# Memory.net
KiCad netlist of a schematic drawn in Altium Designer
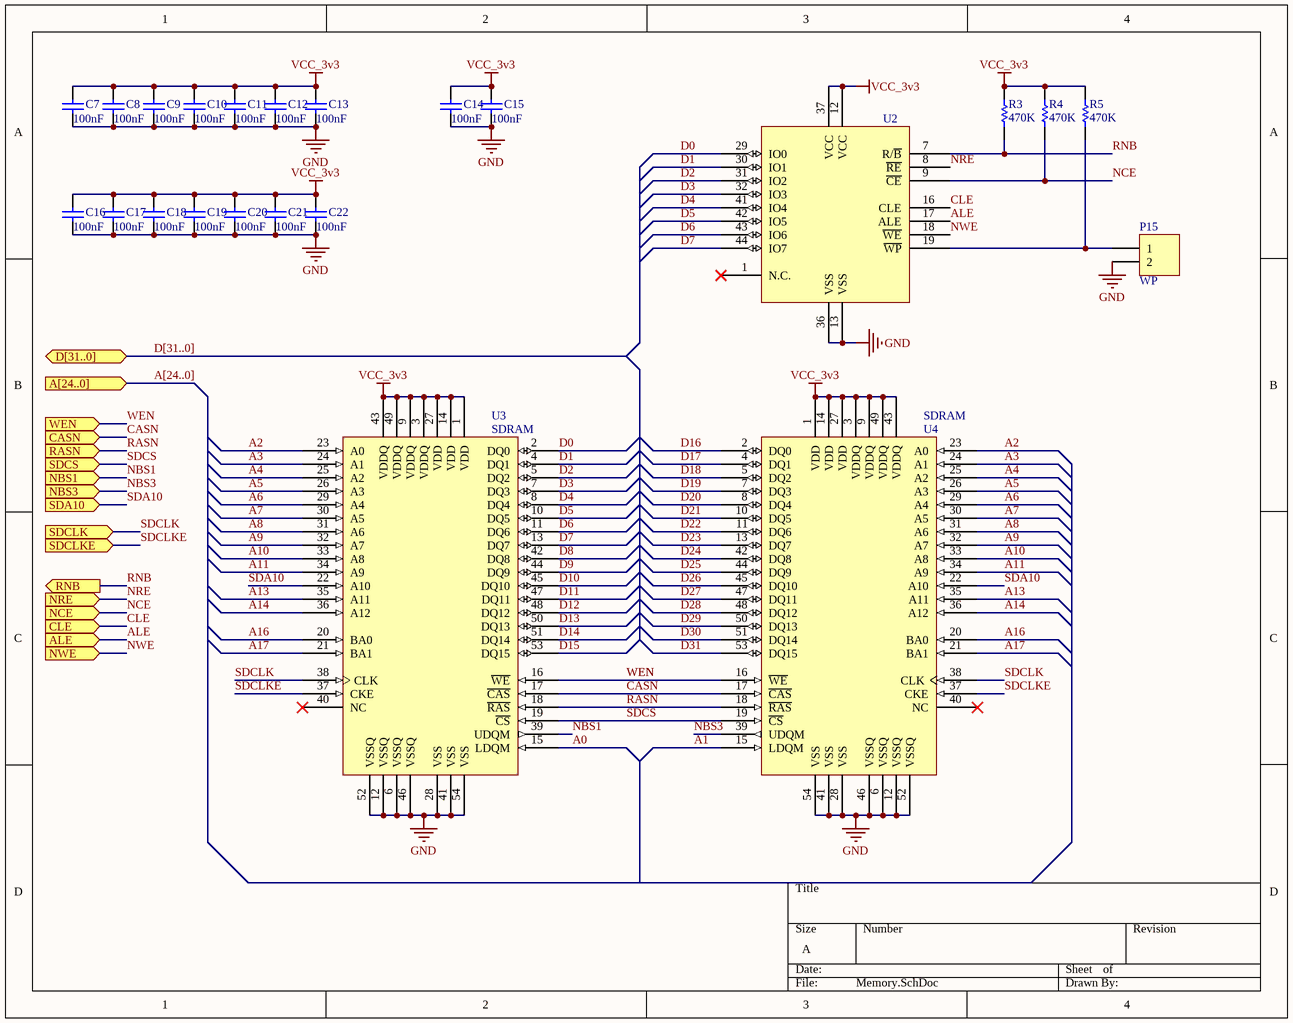
[diagram p0: Memory.SchDoc]

(export (version "E")
  (design (tool "Eeschema 10.0.6"))
  (components
    (comp (ref "C7")
      (value "100nF")
      (footprint "0603PKG")
      (description "Capacitor")
      (fields (field (name "Comment") "Cap") (field (name "PUBLISHER") "Altium Limited"))
      (libsource (lib "Miscellaneous Devices") (part "Cap"))
    )
    (comp (ref "C8")
      (value "100nF")
      (footprint "0603PKG")
      (description "Capacitor")
      (fields (field (name "Comment") "Cap") (field (name "PUBLISHER") "Altium Limited"))
      (libsource (lib "Miscellaneous Devices") (part "Cap"))
    )
    (comp (ref "C9")
      (value "100nF")
      (footprint "0603PKG")
      (description "Capacitor")
      (fields (field (name "Comment") "Cap") (field (name "PUBLISHER") "Altium Limited"))
      (libsource (lib "Miscellaneous Devices") (part "Cap"))
    )
    (comp (ref "C10")
      (value "100nF")
      (footprint "0603PKG")
      (description "Capacitor")
      (fields (field (name "Comment") "Cap") (field (name "PUBLISHER") "Altium Limited"))
      (libsource (lib "Miscellaneous Devices") (part "Cap"))
    )
    (comp (ref "C11")
      (value "100nF")
      (footprint "0603PKG")
      (description "Capacitor")
      (fields (field (name "Comment") "Cap") (field (name "PUBLISHER") "Altium Limited"))
      (libsource (lib "Miscellaneous Devices") (part "Cap"))
    )
    (comp (ref "C12")
      (value "100nF")
      (footprint "0603PKG")
      (description "Capacitor")
      (fields (field (name "Comment") "Cap") (field (name "PUBLISHER") "Altium Limited"))
      (libsource (lib "Miscellaneous Devices") (part "Cap"))
    )
    (comp (ref "C13")
      (value "100nF")
      (footprint "0603PKG")
      (description "Capacitor")
      (fields (field (name "Comment") "Cap") (field (name "PUBLISHER") "Altium Limited"))
      (libsource (lib "Miscellaneous Devices") (part "Cap"))
    )
    (comp (ref "C14")
      (value "100nF")
      (footprint "C0805")
      (description "Capacitor")
      (fields (field (name "Comment") "Cap") (field (name "PUBLISHER") "Altium Limited"))
      (libsource (lib "Miscellaneous Devices") (part "Cap"))
    )
    (comp (ref "C15")
      (value "100nF")
      (footprint "C0805")
      (description "Capacitor")
      (fields (field (name "Comment") "Cap") (field (name "PUBLISHER") "Altium Limited"))
      (libsource (lib "Miscellaneous Devices") (part "Cap"))
    )
    (comp (ref "C16")
      (value "100nF")
      (footprint "0603PKG")
      (description "Capacitor")
      (fields (field (name "Comment") "Cap") (field (name "PUBLISHER") "Altium Limited"))
      (libsource (lib "Miscellaneous Devices") (part "Cap"))
    )
    (comp (ref "C17")
      (value "100nF")
      (footprint "0603PKG")
      (description "Capacitor")
      (fields (field (name "Comment") "Cap") (field (name "PUBLISHER") "Altium Limited"))
      (libsource (lib "Miscellaneous Devices") (part "Cap"))
    )
    (comp (ref "C18")
      (value "100nF")
      (footprint "0603PKG")
      (description "Capacitor")
      (fields (field (name "Comment") "Cap") (field (name "PUBLISHER") "Altium Limited"))
      (libsource (lib "Miscellaneous Devices") (part "Cap"))
    )
    (comp (ref "C19")
      (value "100nF")
      (footprint "0603PKG")
      (description "Capacitor")
      (fields (field (name "Comment") "Cap") (field (name "PUBLISHER") "Altium Limited"))
      (libsource (lib "Miscellaneous Devices") (part "Cap"))
    )
    (comp (ref "C20")
      (value "100nF")
      (footprint "0603PKG")
      (description "Capacitor")
      (fields (field (name "Comment") "Cap") (field (name "PUBLISHER") "Altium Limited"))
      (libsource (lib "Miscellaneous Devices") (part "Cap"))
    )
    (comp (ref "C21")
      (value "100nF")
      (footprint "0603PKG")
      (description "Capacitor")
      (fields (field (name "Comment") "Cap") (field (name "PUBLISHER") "Altium Limited"))
      (libsource (lib "Miscellaneous Devices") (part "Cap"))
    )
    (comp (ref "C22")
      (value "100nF")
      (footprint "0603PKG")
      (description "Capacitor")
      (fields (field (name "Comment") "Cap") (field (name "PUBLISHER") "Altium Limited"))
      (libsource (lib "Miscellaneous Devices") (part "Cap"))
    )
    (comp (ref "P15")
      (value "WP")
      (footprint "HDR1X2")
      (description "Header, 2-Pin")
      (fields (field (name "PUBLISHER") "Altium Limited"))
      (libsource (lib "Miscellaneous Connectors") (part "Header 2"))
    )
    (comp (ref "R3")
      (value "470K")
      (footprint "C0805")
      (description "Semiconductor Resistor")
      (fields (field (name "Comment") "Res Semi") (field (name "PUBLISHER") "Altium Limited"))
      (libsource (lib "Miscellaneous Devices") (part "Res Semi"))
    )
    (comp (ref "R4")
      (value "470K")
      (footprint "C0805")
      (description "Semiconductor Resistor")
      (fields (field (name "Comment") "Res Semi") (field (name "PUBLISHER") "Altium Limited"))
      (libsource (lib "Miscellaneous Devices") (part "Res Semi"))
    )
    (comp (ref "R5")
      (value "470K")
      (footprint "C0805")
      (description "Semiconductor Resistor")
      (fields (field (name "Comment") "Res Semi") (field (name "PUBLISHER") "Altium Limited"))
      (libsource (lib "Miscellaneous Devices") (part "Res Semi"))
    )
    (comp (ref "U2")
      (value "NAND FLASH")
      (footprint "TSSOP-48")
      (libsource (lib "Connector_IntLib") (part "K9F2G08U0A"))
    )
    (comp (ref "U3") (value "SDRAM") (footprint "TSOP54_Pin") (libsource (lib "") (part "K4S561632C_1")))
    (comp (ref "U4")
      (value "SDRAM")
      (footprint "TSOP54_Pin")
      (libsource (lib "Conn_Schlib") (part "K4S561632C"))
    )
  )
  (nets
    (net (code "10") (name "/A0") (class "Default")
      (node (ref "U3") (pin "15") (pinfunction "LDQM_15") (pintype "input"))
    )
    (net (code "11") (name "/A1") (class "Default")
      (node (ref "U4") (pin "15") (pinfunction "LDQM_15") (pintype "input"))
    )
    (net (code "12") (name "/A2") (class "Default")
      (node (ref "U3") (pin "23") (pinfunction "A0_23") (pintype "input"))
      (node (ref "U4") (pin "23") (pinfunction "A0_23") (pintype "input"))
    )
    (net (code "13") (name "/A3") (class "Default")
      (node (ref "U3") (pin "24") (pinfunction "A1_24") (pintype "input"))
      (node (ref "U4") (pin "24") (pinfunction "A1_24") (pintype "input"))
    )
    (net (code "14") (name "/A4") (class "Default")
      (node (ref "U3") (pin "25") (pinfunction "A2_25") (pintype "input"))
      (node (ref "U4") (pin "25") (pinfunction "A2_25") (pintype "input"))
    )
    (net (code "15") (name "/A5") (class "Default")
      (node (ref "U3") (pin "26") (pinfunction "A3_26") (pintype "input"))
      (node (ref "U4") (pin "26") (pinfunction "A3_26") (pintype "input"))
    )
    (net (code "16") (name "/A6") (class "Default")
      (node (ref "U3") (pin "29") (pinfunction "A4_29") (pintype "input"))
      (node (ref "U4") (pin "29") (pinfunction "A4_29") (pintype "input"))
    )
    (net (code "17") (name "/A7") (class "Default")
      (node (ref "U3") (pin "30") (pinfunction "A5_30") (pintype "input"))
      (node (ref "U4") (pin "30") (pinfunction "A5_30") (pintype "input"))
    )
    (net (code "18") (name "/A8") (class "Default")
      (node (ref "U3") (pin "31") (pinfunction "A6_31") (pintype "input"))
      (node (ref "U4") (pin "31") (pinfunction "A6_31") (pintype "input"))
    )
    (net (code "19") (name "/A9") (class "Default")
      (node (ref "U3") (pin "32") (pinfunction "A7_32") (pintype "input"))
      (node (ref "U4") (pin "32") (pinfunction "A7_32") (pintype "input"))
    )
    (net (code "20") (name "/A10") (class "Default")
      (node (ref "U3") (pin "33") (pinfunction "A8_33") (pintype "input"))
      (node (ref "U4") (pin "33") (pinfunction "A8_33") (pintype "input"))
    )
    (net (code "21") (name "/A11") (class "Default")
      (node (ref "U3") (pin "34") (pinfunction "A9_34") (pintype "input"))
      (node (ref "U4") (pin "34") (pinfunction "A9_34") (pintype "input"))
    )
    (net (code "22") (name "/A13") (class "Default")
      (node (ref "U3") (pin "35") (pinfunction "A11_35") (pintype "input"))
      (node (ref "U4") (pin "35") (pinfunction "A11_35") (pintype "input"))
    )
    (net (code "23") (name "/A14") (class "Default")
      (node (ref "U3") (pin "36") (pinfunction "A12_36") (pintype "input"))
      (node (ref "U4") (pin "36") (pinfunction "A12_36") (pintype "input"))
    )
    (net (code "24") (name "/A16") (class "Default")
      (node (ref "U3") (pin "20") (pinfunction "BA0_20") (pintype "input"))
      (node (ref "U4") (pin "20") (pinfunction "BA0_20") (pintype "input"))
    )
    (net (code "25") (name "/A17") (class "Default")
      (node (ref "U3") (pin "21") (pinfunction "BA1_21") (pintype "input"))
      (node (ref "U4") (pin "21") (pinfunction "BA1_21") (pintype "input"))
    )
    (net (code "26") (name "/ALE") (class "Default")
      (node (ref "U2") (pin "17") (pinfunction "ALE_17") (pintype "passive"))
    )
    (net (code "28") (name "/CASN") (class "Default")
      (node (ref "U3") (pin "17") (pinfunction "~{CAS}_17") (pintype "input"))
      (node (ref "U4") (pin "17") (pinfunction "~{CAS}_17") (pintype "input"))
    )
    (net (code "29") (name "/CLE") (class "Default")
      (node (ref "U2") (pin "16") (pinfunction "CLE_16") (pintype "passive"))
    )
    (net (code "30") (name "/D0") (class "Default")
      (node (ref "U2") (pin "29") (pinfunction "IO0_29") (pintype "bidirectional"))
      (node (ref "U3") (pin "2") (pinfunction "DQ0_2") (pintype "bidirectional"))
    )
    (net (code "31") (name "/D1") (class "Default")
      (node (ref "U2") (pin "30") (pinfunction "IO1_30") (pintype "bidirectional"))
      (node (ref "U3") (pin "4") (pinfunction "DQ1_4") (pintype "bidirectional"))
    )
    (net (code "32") (name "/D2") (class "Default")
      (node (ref "U2") (pin "31") (pinfunction "IO2_31") (pintype "bidirectional"))
      (node (ref "U3") (pin "5") (pinfunction "DQ2_5") (pintype "bidirectional"))
    )
    (net (code "33") (name "/D3") (class "Default")
      (node (ref "U2") (pin "32") (pinfunction "IO3_32") (pintype "bidirectional"))
      (node (ref "U3") (pin "7") (pinfunction "DQ3_7") (pintype "bidirectional"))
    )
    (net (code "34") (name "/D4") (class "Default")
      (node (ref "U2") (pin "41") (pinfunction "IO4_41") (pintype "bidirectional"))
      (node (ref "U3") (pin "8") (pinfunction "DQ4_8") (pintype "bidirectional"))
    )
    (net (code "35") (name "/D5") (class "Default")
      (node (ref "U2") (pin "42") (pinfunction "IO5_42") (pintype "bidirectional"))
      (node (ref "U3") (pin "10") (pinfunction "DQ5_10") (pintype "bidirectional"))
    )
    (net (code "36") (name "/D6") (class "Default")
      (node (ref "U2") (pin "43") (pinfunction "IO6_43") (pintype "bidirectional"))
      (node (ref "U3") (pin "11") (pinfunction "DQ6_11") (pintype "bidirectional"))
    )
    (net (code "37") (name "/D7") (class "Default")
      (node (ref "U2") (pin "44") (pinfunction "IO7_44") (pintype "bidirectional"))
      (node (ref "U3") (pin "13") (pinfunction "DQ7_13") (pintype "bidirectional"))
    )
    (net (code "38") (name "/D8") (class "Default")
      (node (ref "U3") (pin "42") (pinfunction "DQ8_42") (pintype "bidirectional"))
    )
    (net (code "39") (name "/D9") (class "Default")
      (node (ref "U3") (pin "44") (pinfunction "DQ9_44") (pintype "bidirectional"))
    )
    (net (code "40") (name "/D10") (class "Default")
      (node (ref "U3") (pin "45") (pinfunction "DQ10_45") (pintype "bidirectional"))
    )
    (net (code "41") (name "/D11") (class "Default")
      (node (ref "U3") (pin "47") (pinfunction "DQ11_47") (pintype "bidirectional"))
    )
    (net (code "42") (name "/D12") (class "Default")
      (node (ref "U3") (pin "48") (pinfunction "DQ12_48") (pintype "bidirectional"))
    )
    (net (code "43") (name "/D13") (class "Default")
      (node (ref "U3") (pin "50") (pinfunction "DQ13_50") (pintype "bidirectional"))
    )
    (net (code "44") (name "/D14") (class "Default")
      (node (ref "U3") (pin "51") (pinfunction "DQ14_51") (pintype "bidirectional"))
    )
    (net (code "45") (name "/D15") (class "Default")
      (node (ref "U3") (pin "53") (pinfunction "DQ15_53") (pintype "bidirectional"))
    )
    (net (code "46") (name "/D16") (class "Default")
      (node (ref "U4") (pin "2") (pinfunction "DQ0_2") (pintype "bidirectional"))
    )
    (net (code "47") (name "/D17") (class "Default")
      (node (ref "U4") (pin "4") (pinfunction "DQ1_4") (pintype "bidirectional"))
    )
    (net (code "48") (name "/D18") (class "Default")
      (node (ref "U4") (pin "5") (pinfunction "DQ2_5") (pintype "bidirectional"))
    )
    (net (code "49") (name "/D19") (class "Default")
      (node (ref "U4") (pin "7") (pinfunction "DQ3_7") (pintype "bidirectional"))
    )
    (net (code "50") (name "/D20") (class "Default")
      (node (ref "U4") (pin "8") (pinfunction "DQ4_8") (pintype "bidirectional"))
    )
    (net (code "51") (name "/D21") (class "Default")
      (node (ref "U4") (pin "10") (pinfunction "DQ5_10") (pintype "bidirectional"))
    )
    (net (code "52") (name "/D22") (class "Default")
      (node (ref "U4") (pin "11") (pinfunction "DQ6_11") (pintype "bidirectional"))
    )
    (net (code "53") (name "/D23") (class "Default")
      (node (ref "U4") (pin "13") (pinfunction "DQ7_13") (pintype "bidirectional"))
    )
    (net (code "54") (name "/D24") (class "Default")
      (node (ref "U4") (pin "42") (pinfunction "DQ8_42") (pintype "bidirectional"))
    )
    (net (code "55") (name "/D25") (class "Default")
      (node (ref "U4") (pin "44") (pinfunction "DQ9_44") (pintype "bidirectional"))
    )
    (net (code "56") (name "/D26") (class "Default")
      (node (ref "U4") (pin "45") (pinfunction "DQ10_45") (pintype "bidirectional"))
    )
    (net (code "57") (name "/D27") (class "Default")
      (node (ref "U4") (pin "47") (pinfunction "DQ11_47") (pintype "bidirectional"))
    )
    (net (code "58") (name "/D28") (class "Default")
      (node (ref "U4") (pin "48") (pinfunction "DQ12_48") (pintype "bidirectional"))
    )
    (net (code "59") (name "/D29") (class "Default")
      (node (ref "U4") (pin "50") (pinfunction "DQ13_50") (pintype "bidirectional"))
    )
    (net (code "60") (name "/D30") (class "Default")
      (node (ref "U4") (pin "51") (pinfunction "DQ14_51") (pintype "bidirectional"))
    )
    (net (code "61") (name "/D31") (class "Default")
      (node (ref "U4") (pin "53") (pinfunction "DQ15_53") (pintype "bidirectional"))
    )
    (net (code "63") (name "/NBS1") (class "Default")
      (node (ref "U3") (pin "39") (pinfunction "UDQM_39") (pintype "output"))
    )
    (net (code "64") (name "/NBS3") (class "Default")
      (node (ref "U4") (pin "39") (pinfunction "UDQM_39") (pintype "output"))
    )
    (net (code "65") (name "/NCE") (class "Default")
      (node (ref "R4") (pin "2") (pinfunction "2_2") (pintype "passive"))
      (node (ref "U2") (pin "9") (pinfunction "~{CE}_9") (pintype "passive"))
    )
    (net (code "66") (name "/NRE") (class "Default")
      (node (ref "U2") (pin "8") (pinfunction "~{RE}_8") (pintype "passive"))
    )
    (net (code "67") (name "/NWE") (class "Default")
      (node (ref "U2") (pin "18") (pinfunction "~{WE}_18") (pintype "passive"))
    )
    (net (code "68") (name "/RASN") (class "Default")
      (node (ref "U3") (pin "18") (pinfunction "~{RAS}_18") (pintype "input"))
      (node (ref "U4") (pin "18") (pinfunction "~{RAS}_18") (pintype "input"))
    )
    (net (code "69") (name "/RNB") (class "Default")
      (node (ref "R3") (pin "2") (pinfunction "2_2") (pintype "passive"))
      (node (ref "U2") (pin "7") (pinfunction "R/~{B}_7") (pintype "passive"))
    )
    (net (code "70") (name "/SDA10") (class "Default")
      (node (ref "U3") (pin "22") (pinfunction "A10_22") (pintype "input"))
      (node (ref "U4") (pin "22") (pinfunction "A10_22") (pintype "input"))
    )
    (net (code "71") (name "/SDCLK") (class "Default")
      (node (ref "U3") (pin "38") (pinfunction "CLK_38") (pintype "input"))
      (node (ref "U4") (pin "38") (pinfunction "CLK_38") (pintype "input"))
    )
    (net (code "72") (name "/SDCLKE") (class "Default")
      (node (ref "U3") (pin "37") (pinfunction "CKE_37") (pintype "input"))
      (node (ref "U4") (pin "37") (pinfunction "CKE_37") (pintype "input"))
    )
    (net (code "73") (name "/SDCS") (class "Default")
      (node (ref "U3") (pin "19") (pinfunction "~{CS}_19") (pintype "input"))
      (node (ref "U4") (pin "19") (pinfunction "~{CS}_19") (pintype "input"))
    )
    (net (code "74") (name "/WEN") (class "Default")
      (node (ref "U3") (pin "16") (pinfunction "~{WE}_16") (pintype "input"))
      (node (ref "U4") (pin "16") (pinfunction "~{WE}_16") (pintype "input"))
    )
    (net (code "75") (name "GND") (class "Default")
      (node (ref "C10") (pin "1") (pinfunction "1_1") (pintype "passive"))
      (node (ref "C11") (pin "1") (pinfunction "1_1") (pintype "passive"))
      (node (ref "C12") (pin "1") (pinfunction "1_1") (pintype "passive"))
      (node (ref "C13") (pin "1") (pinfunction "1_1") (pintype "passive"))
      (node (ref "C14") (pin "1") (pinfunction "1_1") (pintype "passive"))
      (node (ref "C15") (pin "1") (pinfunction "1_1") (pintype "passive"))
      (node (ref "C16") (pin "1") (pinfunction "1_1") (pintype "passive"))
      (node (ref "C17") (pin "1") (pinfunction "1_1") (pintype "passive"))
      (node (ref "C18") (pin "1") (pinfunction "1_1") (pintype "passive"))
      (node (ref "C19") (pin "1") (pinfunction "1_1") (pintype "passive"))
      (node (ref "C20") (pin "1") (pinfunction "1_1") (pintype "passive"))
      (node (ref "C21") (pin "1") (pinfunction "1_1") (pintype "passive"))
      (node (ref "C22") (pin "1") (pinfunction "1_1") (pintype "passive"))
      (node (ref "C7") (pin "1") (pinfunction "1_1") (pintype "passive"))
      (node (ref "C8") (pin "1") (pinfunction "1_1") (pintype "passive"))
      (node (ref "C9") (pin "1") (pinfunction "1_1") (pintype "passive"))
      (node (ref "P15") (pin "2") (pinfunction "2_2") (pintype "passive"))
      (node (ref "U2") (pin "13") (pinfunction "VSS_13") (pintype "power_in"))
      (node (ref "U2") (pin "36") (pinfunction "VSS_36") (pintype "power_in"))
      (node (ref "U3") (pin "12") (pinfunction "VSSQ_12") (pintype "power_in"))
      (node (ref "U3") (pin "28") (pinfunction "VSS_28") (pintype "power_in"))
      (node (ref "U3") (pin "41") (pinfunction "VSS_41") (pintype "power_in"))
      (node (ref "U3") (pin "46") (pinfunction "VSSQ_46") (pintype "power_in"))
      (node (ref "U3") (pin "52") (pinfunction "VSSQ_52") (pintype "power_in"))
      (node (ref "U3") (pin "54") (pinfunction "VSS_54") (pintype "power_in"))
      (node (ref "U3") (pin "6") (pinfunction "VSSQ_6") (pintype "power_in"))
      (node (ref "U4") (pin "12") (pinfunction "VSSQ_12") (pintype "power_in"))
      (node (ref "U4") (pin "28") (pinfunction "VSS_28") (pintype "power_in"))
      (node (ref "U4") (pin "41") (pinfunction "VSS_41") (pintype "power_in"))
      (node (ref "U4") (pin "46") (pinfunction "VSSQ_46") (pintype "power_in"))
      (node (ref "U4") (pin "52") (pinfunction "VSSQ_52") (pintype "power_in"))
      (node (ref "U4") (pin "54") (pinfunction "VSS_54") (pintype "power_in"))
      (node (ref "U4") (pin "6") (pinfunction "VSSQ_6") (pintype "power_in"))
    )
    (net (code "76") (name "Net-(U2-~{WP})") (class "Default")
      (node (ref "P15") (pin "1") (pinfunction "1_1") (pintype "passive"))
      (node (ref "R5") (pin "2") (pinfunction "2_2") (pintype "passive"))
      (node (ref "U2") (pin "19") (pinfunction "~{WP}_19") (pintype "passive"))
    )
    (net (code "77") (name "VCC_3v3") (class "Default")
      (node (ref "C10") (pin "2") (pinfunction "2_2") (pintype "passive"))
      (node (ref "C11") (pin "2") (pinfunction "2_2") (pintype "passive"))
      (node (ref "C12") (pin "2") (pinfunction "2_2") (pintype "passive"))
      (node (ref "C13") (pin "2") (pinfunction "2_2") (pintype "passive"))
      (node (ref "C14") (pin "2") (pinfunction "2_2") (pintype "passive"))
      (node (ref "C15") (pin "2") (pinfunction "2_2") (pintype "passive"))
      (node (ref "C16") (pin "2") (pinfunction "2_2") (pintype "passive"))
      (node (ref "C17") (pin "2") (pinfunction "2_2") (pintype "passive"))
      (node (ref "C18") (pin "2") (pinfunction "2_2") (pintype "passive"))
      (node (ref "C19") (pin "2") (pinfunction "2_2") (pintype "passive"))
      (node (ref "C20") (pin "2") (pinfunction "2_2") (pintype "passive"))
      (node (ref "C21") (pin "2") (pinfunction "2_2") (pintype "passive"))
      (node (ref "C22") (pin "2") (pinfunction "2_2") (pintype "passive"))
      (node (ref "C7") (pin "2") (pinfunction "2_2") (pintype "passive"))
      (node (ref "C8") (pin "2") (pinfunction "2_2") (pintype "passive"))
      (node (ref "C9") (pin "2") (pinfunction "2_2") (pintype "passive"))
      (node (ref "R3") (pin "1") (pinfunction "1_1") (pintype "passive"))
      (node (ref "R4") (pin "1") (pinfunction "1_1") (pintype "passive"))
      (node (ref "R5") (pin "1") (pinfunction "1_1") (pintype "passive"))
      (node (ref "U2") (pin "12") (pinfunction "VCC_12") (pintype "power_in"))
      (node (ref "U2") (pin "37") (pinfunction "VCC_37") (pintype "power_in"))
      (node (ref "U3") (pin "1") (pinfunction "VDD_1") (pintype "power_in"))
      (node (ref "U3") (pin "14") (pinfunction "VDD_14") (pintype "power_in"))
      (node (ref "U3") (pin "27") (pinfunction "VDD_27") (pintype "power_in"))
      (node (ref "U3") (pin "3") (pinfunction "VDDQ_3") (pintype "power_in"))
      (node (ref "U3") (pin "43") (pinfunction "VDDQ_43") (pintype "power_in"))
      (node (ref "U3") (pin "49") (pinfunction "VDDQ_49") (pintype "power_in"))
      (node (ref "U3") (pin "9") (pinfunction "VDDQ_9") (pintype "power_in"))
      (node (ref "U4") (pin "1") (pinfunction "VDD_1") (pintype "power_in"))
      (node (ref "U4") (pin "14") (pinfunction "VDD_14") (pintype "power_in"))
      (node (ref "U4") (pin "27") (pinfunction "VDD_27") (pintype "power_in"))
      (node (ref "U4") (pin "3") (pinfunction "VDDQ_3") (pintype "power_in"))
      (node (ref "U4") (pin "43") (pinfunction "VDDQ_43") (pintype "power_in"))
      (node (ref "U4") (pin "49") (pinfunction "VDDQ_49") (pintype "power_in"))
      (node (ref "U4") (pin "9") (pinfunction "VDDQ_9") (pintype "power_in"))
    )
    (net (code "78") (name "unconnected-(U2-N.C.-Pad1)") (class "Default")
      (node (ref "U2") (pin "1") (pinfunction "N.C._1") (pintype "passive+no_connect"))
    )
    (net (code "79") (name "unconnected-(U3-NC-Pad40)") (class "Default")
      (node (ref "U3") (pin "40") (pinfunction "NC_40") (pintype "passive+no_connect"))
    )
    (net (code "80") (name "unconnected-(U4-NC-Pad40)") (class "Default")
      (node (ref "U4") (pin "40") (pinfunction "NC_40") (pintype "passive+no_connect"))
    )
  )
)
